# hometrainer.net
KiCad netlist of a schematic drawn in Altium Designer
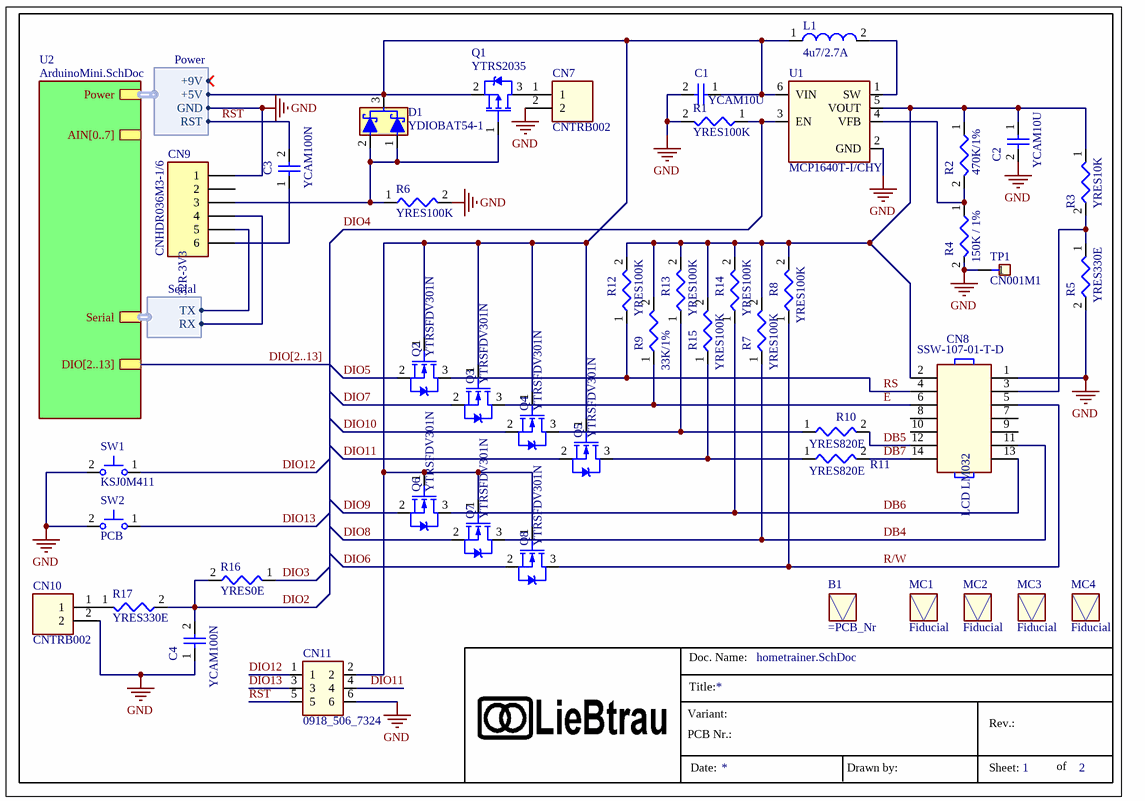
[diagram p0: hometrainer.SchDoc]

(export (version "E")
  (design (tool "Eeschema 10.0.6"))
  (components
    (comp (ref "B1")
      (value "~")
      (footprint "MC_BoardNr")
      (fields (field (name "PART NUMBER") "BARE_PCB"))
      (libsource (lib "Testing") (part "BD_PCB"))
    )
    (comp (ref "C1") (value "YCAM10U") (footprint "CA_1206") (libsource (lib "Testing") (part "CA_NONPOL")))
    (comp (ref "C2") (value "YCAM10U") (footprint "CA_1206") (libsource (lib "Testing") (part "CA_NONPOL")))
    (comp (ref "C3") (value "YCAM100N") (footprint "CA_1206") (libsource (lib "Testing") (part "CA_NONPOL")))
    (comp (ref "C4") (value "YCAM100N") (footprint "CA_1206") (libsource (lib "Testing") (part "CA_NONPOL")))
    (comp (ref "CN7") (value "CNTRB002") (footprint "CN_MKDSN 1,5/2") (libsource (lib "") (part "CN_2P_1")))
    (comp (ref "CN8")
      (value "SSW-107-01-T-D")
      (footprint "CN_SCKT2X7")
      (fields (field (name "MANUFACTURER") "Samtec"))
      (libsource (lib "Testing") (part "CN_2x7P"))
    )
    (comp (ref "CN9")
      (value "CNHDR036M3-1/6")
      (footprint "CN_HDR1X6")
      (libsource (lib "Testing") (part "CN_6P"))
    )
    (comp (ref "CN10")
      (value "CNTRB002")
      (footprint "CN_MKDSN 1,5/2")
      (libsource (lib "Testing") (part "CN_2P"))
    )
    (comp (ref "CN11")
      (value "0918_506_7324")
      (footprint "CN_HARTING_918506X324")
      (fields (field (name "MANUFACTURER") "Harting"))
      (libsource (lib "Testing") (part "CN_2x3P"))
    )
    (comp (ref "D1")
      (value "YDIOBAT54-1")
      (footprint "SC_SOT23")
      (description "Dual Schottky Barrier Diode Common Cathode")
      (fields (field (name "MANUFACTURER") "Fairchild Semiconductor"))
      (libsource (lib "Testing") (part "DI_SCHOTTKY_2_CC"))
    )
    (comp (ref "L1")
      (value "4u7/2.7A")
      (footprint "CL_STD_2220")
      (fields (field (name "PART NUMBER") "LQH55DN4R7M03L") (field (name "MANUFACTURER") "Murata"))
      (libsource (lib "Testing") (part "CL_COIL"))
    )
    (comp (ref "MC1")
      (value "Fiducial")
      (footprint "MC_FIDUCIAL")
      (libsource (lib "Testing") (part "MC_MechPart_No_BOM"))
    )
    (comp (ref "MC2")
      (value "Fiducial")
      (footprint "MC_FIDUCIAL")
      (libsource (lib "Testing") (part "MC_MechPart_No_BOM"))
    )
    (comp (ref "MC3")
      (value "Fiducial")
      (footprint "MC_FIDUCIAL")
      (libsource (lib "Testing") (part "MC_MechPart_No_BOM"))
    )
    (comp (ref "MC4")
      (value "Fiducial")
      (footprint "MC_FIDUCIAL")
      (libsource (lib "Testing") (part "MC_MechPart_No_BOM"))
    )
    (comp (ref "Q1")
      (value "YTRS2035")
      (footprint "SC_SOT23")
      (fields (field (name "MANUFACTURER") "Diodes Inc."))
      (libsource (lib "Testing") (part "TR_PMOS"))
    )
    (comp (ref "Q2")
      (value "YTRSFDV301N")
      (footprint "SC_SOT23")
      (fields (field (name "MANUFACTURER") "FAIRCHILD SEMICONDUCTOR"))
      (libsource (lib "Testing") (part "TR_NMOS"))
    )
    (comp (ref "Q3")
      (value "YTRSFDV301N")
      (footprint "SC_SOT23")
      (fields (field (name "MANUFACTURER") "FAIRCHILD SEMICONDUCTOR"))
      (libsource (lib "Testing") (part "TR_NMOS"))
    )
    (comp (ref "Q4")
      (value "YTRSFDV301N")
      (footprint "SC_SOT23")
      (fields (field (name "MANUFACTURER") "FAIRCHILD SEMICONDUCTOR"))
      (libsource (lib "Testing") (part "TR_NMOS"))
    )
    (comp (ref "Q5")
      (value "YTRSFDV301N")
      (footprint "SC_SOT23")
      (fields (field (name "MANUFACTURER") "FAIRCHILD SEMICONDUCTOR"))
      (libsource (lib "Testing") (part "TR_NMOS"))
    )
    (comp (ref "Q6")
      (value "YTRSFDV301N")
      (footprint "SC_SOT23")
      (fields (field (name "MANUFACTURER") "FAIRCHILD SEMICONDUCTOR"))
      (libsource (lib "Testing") (part "TR_NMOS"))
    )
    (comp (ref "Q7")
      (value "YTRSFDV301N")
      (footprint "SC_SOT23")
      (fields (field (name "MANUFACTURER") "FAIRCHILD SEMICONDUCTOR"))
      (libsource (lib "Testing") (part "TR_NMOS"))
    )
    (comp (ref "Q8")
      (value "YTRSFDV301N")
      (footprint "SC_SOT23")
      (fields (field (name "MANUFACTURER") "FAIRCHILD SEMICONDUCTOR"))
      (libsource (lib "Testing") (part "TR_NMOS"))
    )
    (comp (ref "R1")
      (value "YRES100K")
      (footprint "RE_1206")
      (description "Resistor")
      (fields (field (name "MANUFACTURER") "Multicomp"))
      (libsource (lib "Testing") (part "RE_RES"))
    )
    (comp (ref "R2")
      (value "470K/1%")
      (footprint "RE_1206")
      (description "Resistor")
      (fields (field (name "PART NUMBER") "CRCW1206470KFKEA") (field (name "MANUFACTURER") "Vishay Draloric"))
      (libsource (lib "Testing") (part "RE_RES"))
    )
    (comp (ref "R3")
      (value "YRES10K")
      (footprint "RE_1206")
      (description "Resistor")
      (fields (field (name "MANUFACTURER") "Vishay Draloric"))
      (libsource (lib "Testing") (part "RE_RES"))
    )
    (comp (ref "R4")
      (value "150K / 1%")
      (footprint "RE_1206")
      (description "Resistor")
      (fields (field (name "PART NUMBER") "RC1206FR-07150KL") (field (name "MANUFACTURER") "Yageo (Phycomp)"))
      (libsource (lib "Testing") (part "RE_RES"))
    )
    (comp (ref "R5")
      (value "YRES330E")
      (footprint "RE_1206")
      (description "Resistor")
      (fields (field (name "MANUFACTURER") "Welwyn"))
      (libsource (lib "Testing") (part "RE_RES"))
    )
    (comp (ref "R6")
      (value "YRES100K")
      (footprint "RE_1206")
      (description "Resistor")
      (fields (field (name "MANUFACTURER") "Multicomp"))
      (libsource (lib "Testing") (part "RE_RES"))
    )
    (comp (ref "R7")
      (value "YRES100K")
      (footprint "RE_1206")
      (description "Resistor")
      (fields (field (name "MANUFACTURER") "Multicomp"))
      (libsource (lib "Testing") (part "RE_RES"))
    )
    (comp (ref "R8")
      (value "YRES100K")
      (footprint "RE_1206")
      (description "Resistor")
      (fields (field (name "MANUFACTURER") "Multicomp"))
      (libsource (lib "Testing") (part "RE_RES"))
    )
    (comp (ref "R9")
      (value "33K/1%")
      (footprint "RE_1206")
      (description "Resistor")
      (fields (field (name "PART NUMBER") "MCMR12X3302FTL") (field (name "MANUFACTURER") "Multicomp"))
      (libsource (lib "Testing") (part "RE_RES"))
    )
    (comp (ref "R10")
      (value "YRES820E")
      (footprint "RE_1206")
      (description "Resistor")
      (libsource (lib "Testing") (part "RE_RES"))
    )
    (comp (ref "R11")
      (value "YRES820E")
      (footprint "RE_1206")
      (description "Resistor")
      (libsource (lib "Testing") (part "RE_RES"))
    )
    (comp (ref "R12")
      (value "YRES100K")
      (footprint "RE_1206")
      (description "Resistor")
      (fields (field (name "MANUFACTURER") "Multicomp"))
      (libsource (lib "Testing") (part "RE_RES"))
    )
    (comp (ref "R13")
      (value "YRES100K")
      (footprint "RE_1206")
      (description "Resistor")
      (fields (field (name "MANUFACTURER") "Multicomp"))
      (libsource (lib "Testing") (part "RE_RES"))
    )
    (comp (ref "R14")
      (value "YRES100K")
      (footprint "RE_1206")
      (description "Resistor")
      (fields (field (name "MANUFACTURER") "Multicomp"))
      (libsource (lib "Testing") (part "RE_RES"))
    )
    (comp (ref "R15")
      (value "YRES100K")
      (footprint "RE_1206")
      (description "Resistor")
      (fields (field (name "MANUFACTURER") "Multicomp"))
      (libsource (lib "Testing") (part "RE_RES"))
    )
    (comp (ref "R16")
      (value "YRES0E")
      (footprint "RE_1206")
      (description "Resistor")
      (fields (field (name "MANUFACTURER") "Vishay Draloric"))
      (libsource (lib "Testing") (part "RE_RES"))
    )
    (comp (ref "R17")
      (value "YRES330E")
      (footprint "RE_1206")
      (description "Resistor")
      (fields (field (name "MANUFACTURER") "Welwyn"))
      (libsource (lib "Testing") (part "RE_RES"))
    )
    (comp (ref "SW1")
      (value "KSJ0M411")
      (footprint "SW_KSJ-M")
      (fields (field (name "MANUFACTURER") "C&K"))
      (libsource (lib "Testing") (part "SW_SPST"))
    )
    (comp (ref "SW2")
      (value "PCB")
      (footprint "SW_PCB")
      (fields (field (name "PART NUMBER") "PCB_SWITCH"))
      (libsource (lib "Testing") (part "SW_SPST"))
    )
    (comp (ref "TP1")
      (value "CN001M1")
      (footprint "CN_TP_TH_1.3mm")
      (libsource (lib "Testing") (part "CN_TESTPIN"))
    )
    (comp (ref "U1")
      (value "MCP1640T-I/CHY")
      (footprint "SC_SOT23-6")
      (fields (field (name "MANUFACTURER") "Microchip"))
      (libsource (lib "Testing") (part "IC_MCP1640"))
    )
  )
  (nets
    (net (code "3") (name "/+5V") (class "Default")
      (node (ref "C1") (pin "1") (pinfunction "1_1") (pintype "passive"))
      (node (ref "CN11") (pin "2") (pinfunction "2_2") (pintype "passive"))
      (node (ref "D1") (pin "3") (pinfunction "C_3") (pintype "passive"))
      (node (ref "L1") (pin "1") (pinfunction "1_1") (pintype "passive"))
      (node (ref "Q1") (pin "2") (pinfunction "S_2") (pintype "passive"))
      (node (ref "Q2") (pin "1") (pinfunction "G_1") (pintype "passive"))
      (node (ref "Q3") (pin "1") (pinfunction "G_1") (pintype "passive"))
      (node (ref "Q4") (pin "1") (pinfunction "G_1") (pintype "passive"))
      (node (ref "Q5") (pin "1") (pinfunction "G_1") (pintype "passive"))
      (node (ref "Q6") (pin "1") (pinfunction "G_1") (pintype "passive"))
      (node (ref "Q7") (pin "1") (pinfunction "G_1") (pintype "passive"))
      (node (ref "Q8") (pin "1") (pinfunction "G_1") (pintype "passive"))
      (node (ref "U1") (pin "6") (pinfunction "VIN_6") (pintype "passive"))
    )
    (net (code "5") (name "/DB4") (class "Default")
      (node (ref "CN8") (pin "11") (pinfunction "11_11") (pintype "passive"))
      (node (ref "Q7") (pin "3") (pinfunction "D_3") (pintype "passive"))
      (node (ref "R7") (pin "1") (pinfunction "1_1") (pintype "passive"))
    )
    (net (code "6") (name "/DB5") (class "Default")
      (node (ref "CN8") (pin "12") (pinfunction "12_12") (pintype "passive"))
      (node (ref "R10") (pin "2") (pinfunction "2_2") (pintype "passive"))
    )
    (net (code "7") (name "/DB6") (class "Default")
      (node (ref "CN8") (pin "13") (pinfunction "13_13") (pintype "passive"))
      (node (ref "Q6") (pin "3") (pinfunction "D_3") (pintype "passive"))
      (node (ref "R14") (pin "1") (pinfunction "1_1") (pintype "passive"))
    )
    (net (code "8") (name "/DB7") (class "Default")
      (node (ref "CN8") (pin "14") (pinfunction "14_14") (pintype "passive"))
      (node (ref "R11") (pin "2") (pinfunction "2_2") (pintype "passive"))
    )
    (net (code "9") (name "/DIO2") (class "Default")
      (node (ref "C4") (pin "2") (pinfunction "2_2") (pintype "passive"))
      (node (ref "R16") (pin "2") (pinfunction "2_2") (pintype "passive"))
      (node (ref "R17") (pin "2") (pinfunction "2_2") (pintype "passive"))
    )
    (net (code "10") (name "/DIO3") (class "Default")
      (node (ref "R16") (pin "1") (pinfunction "1_1") (pintype "passive"))
    )
    (net (code "11") (name "/DIO4") (class "Default")
      (node (ref "R1") (pin "1") (pinfunction "1_1") (pintype "passive"))
      (node (ref "U1") (pin "3") (pinfunction "EN_3") (pintype "passive"))
    )
    (net (code "12") (name "/DIO5") (class "Default")
      (node (ref "Q2") (pin "2") (pinfunction "S_2") (pintype "passive"))
    )
    (net (code "13") (name "/DIO6") (class "Default")
      (node (ref "Q8") (pin "2") (pinfunction "S_2") (pintype "passive"))
    )
    (net (code "14") (name "/DIO7") (class "Default")
      (node (ref "Q3") (pin "2") (pinfunction "S_2") (pintype "passive"))
    )
    (net (code "15") (name "/DIO8") (class "Default")
      (node (ref "Q7") (pin "2") (pinfunction "S_2") (pintype "passive"))
    )
    (net (code "16") (name "/DIO9") (class "Default")
      (node (ref "Q6") (pin "2") (pinfunction "S_2") (pintype "passive"))
    )
    (net (code "17") (name "/DIO10") (class "Default")
      (node (ref "Q4") (pin "2") (pinfunction "S_2") (pintype "passive"))
    )
    (net (code "18") (name "/DIO11") (class "Default")
      (node (ref "CN11") (pin "4") (pinfunction "4_4") (pintype "passive"))
      (node (ref "Q5") (pin "2") (pinfunction "S_2") (pintype "passive"))
    )
    (net (code "19") (name "/DIO12") (class "Default")
      (node (ref "CN11") (pin "1") (pinfunction "1_1") (pintype "passive"))
      (node (ref "SW1") (pin "1") (pinfunction "1_1") (pintype "passive"))
    )
    (net (code "20") (name "/DIO13") (class "Default")
      (node (ref "CN11") (pin "3") (pinfunction "3_3") (pintype "passive"))
      (node (ref "SW2") (pin "1") (pinfunction "1_1") (pintype "passive"))
    )
    (net (code "22") (name "/E") (class "Default")
      (node (ref "CN8") (pin "6") (pinfunction "6_6") (pintype "passive"))
      (node (ref "Q3") (pin "3") (pinfunction "D_3") (pintype "passive"))
      (node (ref "R9") (pin "1") (pinfunction "1_1") (pintype "passive"))
    )
    (net (code "23") (name "/RS") (class "Default")
      (node (ref "CN8") (pin "4") (pinfunction "4_4") (pintype "passive"))
      (node (ref "Q2") (pin "3") (pinfunction "D_3") (pintype "passive"))
      (node (ref "R12") (pin "1") (pinfunction "1_1") (pintype "passive"))
    )
    (net (code "24") (name "/RST") (class "Default")
      (node (ref "C3") (pin "2") (pinfunction "2_2") (pintype "passive"))
      (node (ref "CN11") (pin "5") (pinfunction "5_5") (pintype "passive"))
    )
    (net (code "25") (name "/RX") (class "Default")
      (node (ref "CN9") (pin "4") (pinfunction "4_4") (pintype "passive"))
    )
    (net (code "26") (name "/R{slash}W") (class "Default")
      (node (ref "CN8") (pin "5") (pinfunction "5_5") (pintype "passive"))
      (node (ref "Q8") (pin "3") (pinfunction "D_3") (pintype "passive"))
      (node (ref "R8") (pin "1") (pinfunction "1_1") (pintype "passive"))
    )
    (net (code "27") (name "/TX") (class "Default")
      (node (ref "CN9") (pin "5") (pinfunction "5_5") (pintype "passive"))
    )
    (net (code "30") (name "GND") (class "Default")
      (node (ref "C1") (pin "2") (pinfunction "2_2") (pintype "passive"))
      (node (ref "C2") (pin "2") (pinfunction "2_2") (pintype "passive"))
      (node (ref "C4") (pin "1") (pinfunction "1_1") (pintype "passive"))
      (node (ref "CN10") (pin "2") (pinfunction "2_2") (pintype "passive"))
      (node (ref "CN11") (pin "6") (pinfunction "6_6") (pintype "passive"))
      (node (ref "CN7") (pin "2") (pinfunction "2_2") (pintype "passive"))
      (node (ref "CN8") (pin "1") (pinfunction "1_1") (pintype "passive"))
      (node (ref "CN9") (pin "1") (pinfunction "1_1") (pintype "passive"))
      (node (ref "R1") (pin "2") (pinfunction "2_2") (pintype "passive"))
      (node (ref "R4") (pin "2") (pinfunction "2_2") (pintype "passive"))
      (node (ref "R5") (pin "2") (pinfunction "2_2") (pintype "passive"))
      (node (ref "R6") (pin "2") (pinfunction "2_2") (pintype "passive"))
      (node (ref "SW1") (pin "2") (pinfunction "2_2") (pintype "passive"))
      (node (ref "SW2") (pin "2") (pinfunction "2_2") (pintype "passive"))
      (node (ref "TP1") (pin "1") (pinfunction "1_1") (pintype "passive"))
      (node (ref "U1") (pin "2") (pinfunction "GND_2") (pintype "passive"))
    )
    (net (code "31") (name "Net-(C3-Pad1)") (class "Default")
      (node (ref "C3") (pin "1") (pinfunction "1_1") (pintype "passive"))
      (node (ref "CN9") (pin "6") (pinfunction "6_6") (pintype "passive"))
    )
    (net (code "32") (name "Net-(CN8-Pad3)") (class "Default")
      (node (ref "CN8") (pin "3") (pinfunction "3_3") (pintype "passive"))
      (node (ref "R3") (pin "2") (pinfunction "2_2") (pintype "passive"))
      (node (ref "R5") (pin "1") (pinfunction "1_1") (pintype "passive"))
    )
    (net (code "33") (name "Net-(CN10-Pad1)") (class "Default")
      (node (ref "CN10") (pin "1") (pinfunction "1_1") (pintype "passive"))
      (node (ref "R17") (pin "1") (pinfunction "1_1") (pintype "passive"))
    )
    (net (code "34") (name "Net-(D1-A1)") (class "Default")
      (node (ref "CN9") (pin "3") (pinfunction "3_3") (pintype "passive"))
      (node (ref "D1") (pin "1") (pinfunction "A1_1") (pintype "passive"))
      (node (ref "D1") (pin "2") (pinfunction "A2_2") (pintype "passive"))
      (node (ref "Q1") (pin "1") (pinfunction "G_1") (pintype "passive"))
      (node (ref "R6") (pin "1") (pinfunction "1_1") (pintype "passive"))
    )
    (net (code "35") (name "Net-(Q1-D)") (class "Default")
      (node (ref "CN7") (pin "1") (pinfunction "1_1") (pintype "passive"))
      (node (ref "Q1") (pin "3") (pinfunction "D_3") (pintype "passive"))
    )
    (net (code "36") (name "Net-(Q4-D)") (class "Default")
      (node (ref "Q4") (pin "3") (pinfunction "D_3") (pintype "passive"))
      (node (ref "R10") (pin "1") (pinfunction "1_1") (pintype "passive"))
      (node (ref "R13") (pin "1") (pinfunction "1_1") (pintype "passive"))
    )
    (net (code "37") (name "Net-(Q5-D)") (class "Default")
      (node (ref "Q5") (pin "3") (pinfunction "D_3") (pintype "passive"))
      (node (ref "R11") (pin "1") (pinfunction "1_1") (pintype "passive"))
      (node (ref "R15") (pin "1") (pinfunction "1_1") (pintype "passive"))
    )
    (net (code "38") (name "Net-(U1-SW)") (class "Default")
      (node (ref "L1") (pin "2") (pinfunction "2_2") (pintype "passive"))
      (node (ref "U1") (pin "1") (pinfunction "SW_1") (pintype "passive"))
    )
    (net (code "39") (name "Net-(U1-VFB)") (class "Default")
      (node (ref "R2") (pin "2") (pinfunction "2_2") (pintype "passive"))
      (node (ref "R4") (pin "1") (pinfunction "1_1") (pintype "passive"))
      (node (ref "U1") (pin "4") (pinfunction "VFB_4") (pintype "passive"))
    )
    (net (code "40") (name "Net-(U1-VOUT)") (class "Default")
      (node (ref "C2") (pin "1") (pinfunction "1_1") (pintype "passive"))
      (node (ref "CN8") (pin "2") (pinfunction "2_2") (pintype "passive"))
      (node (ref "R12") (pin "2") (pinfunction "2_2") (pintype "passive"))
      (node (ref "R13") (pin "2") (pinfunction "2_2") (pintype "passive"))
      (node (ref "R14") (pin "2") (pinfunction "2_2") (pintype "passive"))
      (node (ref "R15") (pin "2") (pinfunction "2_2") (pintype "passive"))
      (node (ref "R2") (pin "1") (pinfunction "1_1") (pintype "passive"))
      (node (ref "R3") (pin "1") (pinfunction "1_1") (pintype "passive"))
      (node (ref "R7") (pin "2") (pinfunction "2_2") (pintype "passive"))
      (node (ref "R8") (pin "2") (pinfunction "2_2") (pintype "passive"))
      (node (ref "R9") (pin "2") (pinfunction "2_2") (pintype "passive"))
      (node (ref "U1") (pin "5") (pinfunction "VOUT_5") (pintype "passive"))
    )
    (net (code "41") (name "unconnected-(CN8-Pad7)") (class "Default")
      (node (ref "CN8") (pin "7") (pinfunction "7_7") (pintype "passive"))
    )
    (net (code "42") (name "unconnected-(CN8-Pad8)") (class "Default")
      (node (ref "CN8") (pin "8") (pinfunction "8_8") (pintype "passive"))
    )
    (net (code "43") (name "unconnected-(CN8-Pad9)") (class "Default")
      (node (ref "CN8") (pin "9") (pinfunction "9_9") (pintype "passive"))
    )
    (net (code "44") (name "unconnected-(CN8-Pad10)") (class "Default")
      (node (ref "CN8") (pin "10") (pinfunction "10_10") (pintype "passive"))
    )
    (net (code "45") (name "unconnected-(CN9-Pad2)") (class "Default")
      (node (ref "CN9") (pin "2") (pinfunction "2_2") (pintype "passive"))
    )
  )
)
